# Schematic_Rev2.net
KiCad netlist of a schematic drawn in Altium Designer
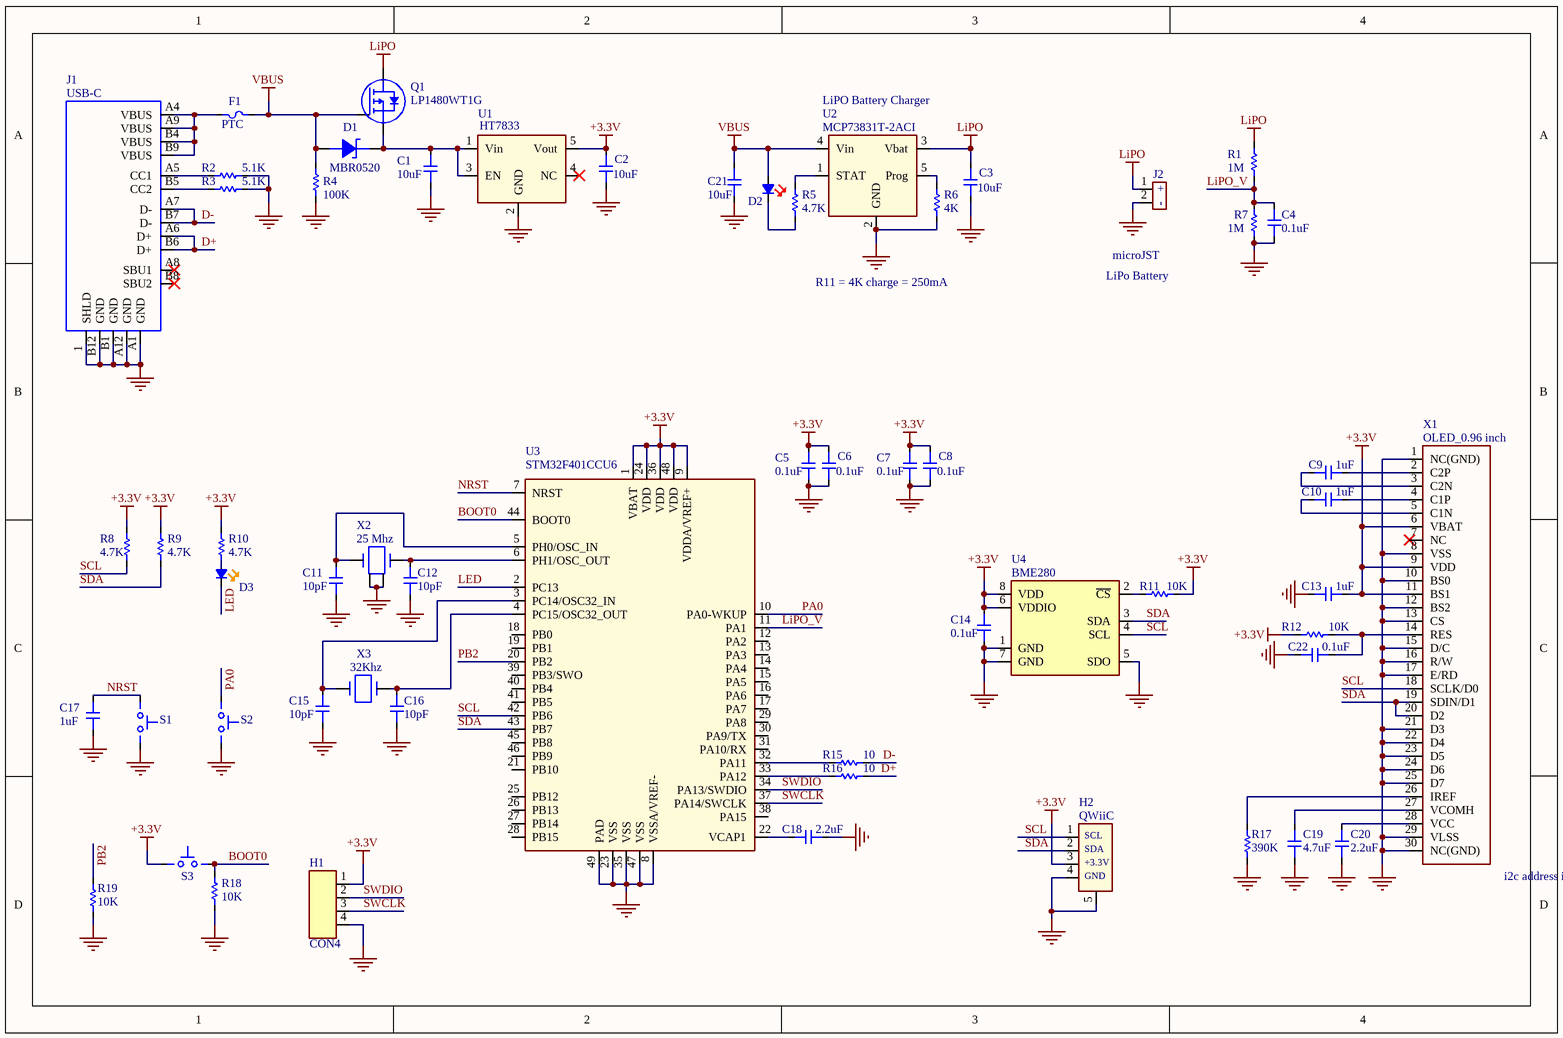
[diagram p0: Schematic_Rev2.SchDoc]

(export (version "E")
  (design (tool "Eeschema 10.0.6"))
  (components
    (comp (ref "C1")
      (value "10uF")
      (footprint "CAPC2012X140N")
      (description "CAP 10uF 0805")
      (libsource (lib "MAR") (part "CAP_0805"))
    )
    (comp (ref "C2")
      (value "10uF")
      (footprint "CAPC2012X140N")
      (description "CAP 10uF 0805")
      (libsource (lib "MAR") (part "CAP_0805"))
    )
    (comp (ref "C3")
      (value "10uF")
      (footprint "CAPC2012X140N")
      (description "CAP 10uF 0805")
      (libsource (lib "MAR") (part "CAP_0805"))
    )
    (comp (ref "C4")
      (value "0.1uF")
      (footprint "CAPC0603X56N")
      (description "CAP 0.1uF 0201")
      (libsource (lib "MAR") (part "CAP_0201"))
    )
    (comp (ref "C5")
      (value "0.1uF")
      (footprint "CAPC1005X56N")
      (description "CAP 0.1uF 0402")
      (libsource (lib "MAR") (part "CAP_0402"))
    )
    (comp (ref "C6")
      (value "0.1uF")
      (footprint "CAPC1005X56N")
      (description "CAP 0.1uF 0402")
      (libsource (lib "MAR") (part "CAP_0402"))
    )
    (comp (ref "C7")
      (value "0.1uF")
      (footprint "CAPC1005X56N")
      (description "CAP 0.1uF 0402")
      (libsource (lib "MAR") (part "CAP_0402"))
    )
    (comp (ref "C8")
      (value "0.1uF")
      (footprint "CAPC1005X56N")
      (description "CAP 0.1uF 0402")
      (libsource (lib "MAR") (part "CAP_0402"))
    )
    (comp (ref "C9")
      (value "1uF")
      (footprint "CAPC1005X56N")
      (description "CAP 1uF 0402")
      (libsource (lib "MAR") (part "CAP_0402"))
    )
    (comp (ref "C10")
      (value "1uF")
      (footprint "CAPC1005X56N")
      (description "CAP 1uF 0402")
      (libsource (lib "MAR") (part "CAP_0402"))
    )
    (comp (ref "C11")
      (value "10pF")
      (footprint "CAPC0603X56N")
      (description "CAP 0.1uF 0201")
      (libsource (lib "MAR") (part "CAP_0201"))
    )
    (comp (ref "C12")
      (value "10pF")
      (footprint "CAPC0603X56N")
      (description "CAP 10pF 0201")
      (libsource (lib "MAR") (part "CAP_0201"))
    )
    (comp (ref "C13")
      (value "1uF")
      (footprint "CAPC1005X56N")
      (description "CAP 1uF 0402")
      (libsource (lib "MAR") (part "CAP_0402"))
    )
    (comp (ref "C14")
      (value "0.1uF")
      (footprint "CAPC0603X56N")
      (description "CAP 0.1uF 0201")
      (libsource (lib "MAR") (part "CAP_0201"))
    )
    (comp (ref "C15")
      (value "10pF")
      (footprint "CAPC0603X56N")
      (description "CAP 0.1uF 0201")
      (libsource (lib "MAR") (part "CAP_0201"))
    )
    (comp (ref "C16")
      (value "10pF")
      (footprint "CAPC0603X56N")
      (description "CAP 10pF 0201")
      (libsource (lib "MAR") (part "CAP_0201"))
    )
    (comp (ref "C17")
      (value "1uF")
      (footprint "CAPC1005X56N")
      (description "CAP 1uF 0402")
      (libsource (lib "MAR") (part "CAP_0402"))
    )
    (comp (ref "C18")
      (value "2.2uF")
      (footprint "CAPC1608X09L")
      (description "CAP 2.2uF 0603")
      (libsource (lib "MAR") (part "CAP_0603"))
    )
    (comp (ref "C19")
      (value "4.7uF")
      (footprint "CAPC1608X09L")
      (description "CAP 4.7uF 0603")
      (libsource (lib "MAR") (part "CAP_0603"))
    )
    (comp (ref "C20")
      (value "2.2uF")
      (footprint "CAPC1608X09L")
      (description "CAP 2.2uF 0603")
      (libsource (lib "MAR") (part "CAP_0603"))
    )
    (comp (ref "C21")
      (value "10uF")
      (footprint "CAPC2012X140N")
      (description "CAP 10uF 0805")
      (libsource (lib "MAR") (part "CAP_0805"))
    )
    (comp (ref "C22")
      (value "0.1uF")
      (footprint "CAPC1005X56N")
      (description "CAP 0.1uF 0402")
      (libsource (lib "MAR") (part "CAP_0402"))
    )
    (comp (ref "D1")
      (value "MBR0520")
      (footprint "SOD123")
      (description "DIODE SCHOTTKY 20V 500MA SOD-123")
      (fields (field (name "MANUFACTURER") "Micro") (field (name "PART_NUMBER") "C78746"))
      (libsource (lib "MAR") (part "MBR0520-TP"))
    )
    (comp (ref "D2")
      (value "Red Led")
      (footprint "LED1005X40N-Red")
      (description "LED Red 0402")
      (fields (field (name "PART_NUMBER") "C364556") (field (name "MANUFACTURER") "Lite-On"))
      (libsource (lib "MAR") (part "LED_0402_SMALL_Red"))
    )
    (comp (ref "D3")
      (value "~")
      (footprint "LED1005X40N-Orange")
      (description "LED Orange 0402")
      (fields (field (name "MANUFACTURER") "Lite-On") (field (name "PART_NUMBER") "C364554"))
      (libsource (lib "MAR") (part "LED_0402_SMALL_Orange"))
    )
    (comp (ref "F1")
      (value "PTC")
      (footprint "RESC1608X06L (0603 FOOTPRINT)")
      (description "PTC FUSE 0.5mA hold, 1A trip 0603")
      (fields (field (name "MANUFACTURER") "JDT Fuse") (field (name "PART_NUMBER") "C2982257"))
      (libsource (lib "MAR") (part "PTC_FUSE_0603"))
    )
    (comp (ref "H1")
      (value "CON4")
      (footprint "HDR1X4-Empty")
      (description "CONN HEADER 4POS .100\" PADS")
      (fields (field (name "PART_NUMBER") "PADS"))
      (libsource (lib "MAR") (part "CON4"))
    )
    (comp (ref "H2")
      (value "QWiiC")
      (footprint "SM04B-SRSS-TB")
      (description "CONN HEADER 4POS .100 R/A QWIIC")
      (fields (field (name "MANUFACTURER") "JST") (field (name "PART_NUMBER") "PRT-14417"))
      (libsource (lib "MAR") (part "SM04B-SRSS-TB"))
    )
    (comp (ref "J1")
      (value "USB-C")
      (footprint "TYPE-C-31-M-12")
      (description "CONN RECPT USB-C")
      (fields (field (name "MANUFACTURER") "KHE") (field (name "PART_NUMBER") "C165948"))
      (libsource (lib "MAR") (part "USB-C"))
    )
    (comp (ref "J2")
      (value "CON2")
      (footprint "JST_Micro_2PIN")
      (description "JST MIcro CONN 2POS")
      (libsource (lib "MAR") (part "JST_Micro_CONN_2PIN"))
    )
    (comp (ref "Q1")
      (value "LP1480WT1G")
      (footprint "SC-70")
      (description "MOSFET P-CH 20V 1.4A SC-70")
      (fields (field (name "MANUFACTURER") "LRC") (field (name "PART_NUMBER") "C172434"))
      (libsource (lib "MAR") (part "LP1480WT1G"))
    )
    (comp (ref "R1")
      (value "1M")
      (footprint "RESC0603X40L (0201 footprint)")
      (description "RES 1M 0201")
      (libsource (lib "MAR") (part "RES_0201"))
    )
    (comp (ref "R2")
      (value "5.1K")
      (footprint "RESC0603X40L (0201 footprint)")
      (description "RES 0201 5.1K")
      (libsource (lib "MAR") (part "RES_0201"))
    )
    (comp (ref "R3")
      (value "5.1K")
      (footprint "RESC0603X40L (0201 footprint)")
      (description "RES 0201 5.1K")
      (libsource (lib "MAR") (part "RES_0201"))
    )
    (comp (ref "R4")
      (value "100K")
      (footprint "RESC0603X40L (0201 footprint)")
      (description "RES 100K 0201")
      (libsource (lib "MAR") (part "RES_0201"))
    )
    (comp (ref "R5")
      (value "4.7K")
      (footprint "RESC0603X40L (0201 footprint)")
      (description "RES 4.7K 0201")
      (libsource (lib "MAR") (part "RES_0201"))
    )
    (comp (ref "R6")
      (value "4K")
      (footprint "RESC0603X40L (0201 footprint)")
      (description "RES 4K 0201")
      (libsource (lib "MAR") (part "RES_0201"))
    )
    (comp (ref "R7")
      (value "1M")
      (footprint "RESC0603X40L (0201 footprint)")
      (description "RES 1M 0201")
      (libsource (lib "MAR") (part "RES_0201"))
    )
    (comp (ref "R8")
      (value "4.7K")
      (footprint "RESC0603X40L (0201 footprint)")
      (description "RES 4.7K 0201")
      (libsource (lib "MAR") (part "RES_0201"))
    )
    (comp (ref "R9")
      (value "4.7K")
      (footprint "RESC0603X40L (0201 footprint)")
      (description "RES 4.7K 0201")
      (libsource (lib "MAR") (part "RES_0201"))
    )
    (comp (ref "R10")
      (value "4.7K")
      (footprint "RESC0603X40L (0201 footprint)")
      (description "RES 4.7K 0201")
      (libsource (lib "MAR") (part "RES_0201"))
    )
    (comp (ref "R11")
      (value "10K")
      (footprint "RESC0603X40L (0201 footprint)")
      (description "RES 10K 0201")
      (libsource (lib "MAR") (part "RES_0201"))
    )
    (comp (ref "R12")
      (value "10K")
      (footprint "RESC0603X40L (0201 footprint)")
      (description "RES 10K 0201")
      (libsource (lib "MAR") (part "RES_0201"))
    )
    (comp (ref "R15")
      (value "10")
      (footprint "RESC0603X40L (0201 footprint)")
      (description "RES 10 0201")
      (libsource (lib "MAR") (part "RES_0201"))
    )
    (comp (ref "R16")
      (value "10")
      (footprint "RESC0603X40L (0201 footprint)")
      (description "RES 10 0201")
      (libsource (lib "MAR") (part "RES_0201"))
    )
    (comp (ref "R17")
      (value "390K")
      (footprint "RESC0603X40L (0201 footprint)")
      (description "RES 390K 0201")
      (libsource (lib "MAR") (part "RES_0201"))
    )
    (comp (ref "R18")
      (value "10K")
      (footprint "RESC0603X40L (0201 footprint)")
      (description "RES 10K 0201")
      (libsource (lib "MAR") (part "RES_0201"))
    )
    (comp (ref "R19")
      (value "10K")
      (footprint "RESC0603X40L (0201 footprint)")
      (description "RES 10K 0201")
      (libsource (lib "MAR") (part "RES_0201"))
    )
    (comp (ref "S1")
      (value "~")
      (footprint "TS-1088R-02526")
      (description "Tactile Micro Switch")
      (fields (field (name "PART_NUMBER") "C455281") (field (name "MANUFACTURER") "XUNPU"))
      (libsource (lib "MAR") (part "TS-1088R-02526"))
    )
    (comp (ref "S2")
      (value "~")
      (footprint "TS-1088R-02526")
      (description "Tactile Micro Switch")
      (fields (field (name "PART_NUMBER") "C455281") (field (name "MANUFACTURER") "XUNPU"))
      (libsource (lib "MAR") (part "TS-1088R-02526"))
    )
    (comp (ref "S3")
      (value "~")
      (footprint "TS-1088R-02526")
      (description "Tactile Micro Switch")
      (fields (field (name "PART_NUMBER") "C455281") (field (name "MANUFACTURER") "XUNPU"))
      (libsource (lib "MAR") (part "TS-1088R-02526"))
    )
    (comp (ref "U1")
      (value "HT7833")
      (footprint "SOT95P280X144-5N")
      (description "IC LDO 3.3V 0.5A SOT23-5")
      (fields (field (name "MANUFACTURER") "Holtek") (field (name "PART_NUMBER") "C164106"))
      (libsource (lib "MAR") (part "HT7833"))
    )
    (comp (ref "U2")
      (value "MCP73831T-2ACI")
      (footprint "SOT95P280X144-5N")
      (description "Charger IC Lithium-Ion/Polymer SOT23-5")
      (fields (field (name "MANUFACTURER") "Microchip") (field (name "PART_NUMBER") "MCP73831T-2ACI/OT"))
      (libsource (lib "MAR") (part "MCP73831T-2ACI/OT"))
    )
    (comp (ref "U3")
      (value "STM32F401CCU6")
      (footprint "QFN48_NEWEST 0.5mm pitch")
      (description "IC MCU 32BIT 256KB FLASH 48LQFN")
      (fields (field (name "MANUFACTURER") "ST Micro"))
      (libsource (lib "MAR") (part "STM32F401CCU6"))
    )
    (comp (ref "U4")
      (value "BME280")
      (footprint "LGA2.5X2.5-8N")
      (description "Gas, Humidity, Pressure, Temperature Sensor I2C,")
      (fields (field (name "MANUFACTURER") "Bosch"))
      (libsource (lib "MAR") (part "BME280"))
    )
    (comp (ref "X1")
      (value "OLED_0.96 inch")
      (footprint "OLED_GLASS 0.96 INCH_TOPSIDE")
      (description "0.96 inch OLED_GLASS")
      (fields (field (name "PART_NUMBER") "ER-OLED0.96-3W") (field (name "MANUFACTURER") "Buy-Display"))
      (libsource (lib "MAR") (part "OLED_GLASS 0.96 inch"))
    )
    (comp (ref "X2")
      (value "25 Mhz")
      (footprint "OSC20X16")
      (description "CRYSTAL 25MHZ 10PF SMD")
      (fields (field (name "PART_NUMBER") "ECS-250-10-37B2-CTN-TR") (field (name "MANUFACTURER") "ECS"))
      (libsource (lib "MAR") (part "25Mhz"))
    )
    (comp (ref "X3")
      (value "32Khz")
      (footprint "TJXM32768K2TGDCNT2T")
      (description "CRYSTAL 32.768 KHZ 12.5PF SMD")
      (fields (field (name "PART_NUMBER") "TJXM32768K2TGDCNT2T") (field (name "MANUFACTURER") "TAE"))
      (libsource (lib "MAR") (part "TJXM32768K2TGDCNT2T"))
    )
  )
  (nets
    (net (code "1") (name "+3.3V") (class "Default")
      (node (ref "C13") (pin "2") (pintype "passive"))
      (node (ref "C14") (pin "1") (pintype "passive"))
      (node (ref "C2") (pin "1") (pintype "passive"))
      (node (ref "C5") (pin "2") (pintype "passive"))
      (node (ref "C6") (pin "2") (pintype "passive"))
      (node (ref "C7") (pin "2") (pintype "passive"))
      (node (ref "C8") (pin "2") (pintype "passive"))
      (node (ref "H1") (pin "1") (pintype "passive"))
      (node (ref "H2") (pin "3") (pintype "passive"))
      (node (ref "R10") (pin "1") (pintype "passive"))
      (node (ref "R11") (pin "2") (pintype "passive"))
      (node (ref "R12") (pin "1") (pintype "passive"))
      (node (ref "R8") (pin "1") (pintype "passive"))
      (node (ref "R9") (pin "1") (pintype "passive"))
      (node (ref "S3") (pin "1") (pinfunction "A_1") (pintype "passive"))
      (node (ref "U1") (pin "5") (pinfunction "Vout_5") (pintype "passive"))
      (node (ref "U3") (pin "1") (pinfunction "VBAT_1") (pintype "power_in"))
      (node (ref "U3") (pin "24") (pinfunction "VDD_24") (pintype "power_in"))
      (node (ref "U3") (pin "36") (pinfunction "VDD_36") (pintype "power_in"))
      (node (ref "U3") (pin "48") (pinfunction "VDD_48") (pintype "power_in"))
      (node (ref "U3") (pin "9") (pinfunction "VDDA/VREF+_9") (pintype "power_in"))
      (node (ref "U4") (pin "6") (pinfunction "VDDIO_6") (pintype "power_in"))
      (node (ref "U4") (pin "8") (pinfunction "VDD_8") (pintype "power_in"))
      (node (ref "X1") (pin "11") (pinfunction "BS1_11") (pintype "passive"))
      (node (ref "X1") (pin "6") (pinfunction "VBAT_6") (pintype "passive"))
      (node (ref "X1") (pin "9") (pinfunction "VDD_9") (pintype "passive"))
    )
    (net (code "2") (name "/BOOT0") (class "Default")
      (node (ref "R18") (pin "1") (pintype "passive"))
      (node (ref "S3") (pin "2") (pinfunction "B_2") (pintype "passive"))
      (node (ref "U3") (pin "44") (pinfunction "BOOT0_44") (pintype "passive"))
    )
    (net (code "3") (name "/D+") (class "Default")
      (node (ref "J1") (pin "A6") (pinfunction "D+_A6") (pintype "power_in"))
      (node (ref "J1") (pin "B6") (pinfunction "D+_B6") (pintype "power_in"))
      (node (ref "R16") (pin "2") (pintype "passive"))
    )
    (net (code "4") (name "/D-") (class "Default")
      (node (ref "J1") (pin "A7") (pinfunction "D-_A7") (pintype "power_in"))
      (node (ref "J1") (pin "B7") (pinfunction "D-_B7") (pintype "power_in"))
      (node (ref "R15") (pin "2") (pintype "passive"))
    )
    (net (code "5") (name "/LED") (class "Default")
      (node (ref "D3") (pin "1") (pintype "passive"))
      (node (ref "U3") (pin "2") (pinfunction "PC13_2") (pintype "passive"))
    )
    (net (code "6") (name "/LiPO_V") (class "Default")
      (node (ref "C4") (pin "1") (pintype "passive"))
      (node (ref "R1") (pin "1") (pintype "passive"))
      (node (ref "R7") (pin "2") (pintype "passive"))
      (node (ref "U3") (pin "11") (pinfunction "PA1_11") (pintype "passive"))
    )
    (net (code "7") (name "/NRST") (class "Default")
      (node (ref "C17") (pin "2") (pintype "passive"))
      (node (ref "S1") (pin "1") (pinfunction "A_1") (pintype "passive"))
      (node (ref "U3") (pin "7") (pinfunction "NRST_7") (pintype "passive"))
    )
    (net (code "8") (name "/PA0") (class "Default")
      (node (ref "S2") (pin "1") (pinfunction "A_1") (pintype "passive"))
      (node (ref "U3") (pin "10") (pinfunction "PA0-WKUP_10") (pintype "passive"))
    )
    (net (code "9") (name "/PB2") (class "Default")
      (node (ref "R19") (pin "2") (pintype "passive"))
      (node (ref "U3") (pin "20") (pinfunction "PB2_20") (pintype "passive"))
    )
    (net (code "10") (name "/SCL") (class "Default")
      (node (ref "H2") (pin "1") (pintype "passive"))
      (node (ref "R8") (pin "2") (pintype "passive"))
      (node (ref "U3") (pin "42") (pinfunction "PB6_42") (pintype "passive"))
      (node (ref "U4") (pin "4") (pinfunction "SCL_4") (pintype "passive"))
      (node (ref "X1") (pin "18") (pinfunction "SCLK/D0_18") (pintype "passive"))
    )
    (net (code "11") (name "/SDA") (class "Default")
      (node (ref "H2") (pin "2") (pintype "passive"))
      (node (ref "R9") (pin "2") (pintype "passive"))
      (node (ref "U3") (pin "43") (pinfunction "PB7_43") (pintype "passive"))
      (node (ref "U4") (pin "3") (pinfunction "SDA_3") (pintype "passive"))
      (node (ref "X1") (pin "19") (pinfunction "SDIN/D1_19") (pintype "passive"))
      (node (ref "X1") (pin "20") (pinfunction "D2_20") (pintype "passive"))
    )
    (net (code "12") (name "/SWCLK") (class "Default")
      (node (ref "H1") (pin "3") (pintype "passive"))
      (node (ref "U3") (pin "37") (pinfunction "PA14/SWCLK_37") (pintype "passive"))
    )
    (net (code "13") (name "/SWDIO") (class "Default")
      (node (ref "H1") (pin "2") (pintype "passive"))
      (node (ref "U3") (pin "34") (pinfunction "PA13/SWDIO_34") (pintype "passive"))
    )
    (net (code "14") (name "GND") (class "Default")
      (node (ref "C1") (pin "2") (pintype "passive"))
      (node (ref "C11") (pin "2") (pintype "passive"))
      (node (ref "C12") (pin "2") (pintype "passive"))
      (node (ref "C13") (pin "1") (pintype "passive"))
      (node (ref "C14") (pin "2") (pintype "passive"))
      (node (ref "C15") (pin "2") (pintype "passive"))
      (node (ref "C16") (pin "2") (pintype "passive"))
      (node (ref "C17") (pin "1") (pintype "passive"))
      (node (ref "C18") (pin "2") (pintype "passive"))
      (node (ref "C19") (pin "1") (pintype "passive"))
      (node (ref "C2") (pin "2") (pintype "passive"))
      (node (ref "C20") (pin "2") (pintype "passive"))
      (node (ref "C21") (pin "2") (pintype "passive"))
      (node (ref "C22") (pin "2") (pintype "passive"))
      (node (ref "C3") (pin "2") (pintype "passive"))
      (node (ref "C4") (pin "2") (pintype "passive"))
      (node (ref "C5") (pin "1") (pintype "passive"))
      (node (ref "C6") (pin "1") (pintype "passive"))
      (node (ref "C7") (pin "1") (pintype "passive"))
      (node (ref "C8") (pin "1") (pintype "passive"))
      (node (ref "H1") (pin "4") (pintype "passive"))
      (node (ref "H2") (pin "4") (pintype "passive"))
      (node (ref "H2") (pin "5") (pintype "passive"))
      (node (ref "J1") (pin "1") (pinfunction "SHLD_1") (pintype "power_in"))
      (node (ref "J1") (pin "A1") (pinfunction "GND_A1") (pintype "power_in"))
      (node (ref "J1") (pin "A12") (pinfunction "GND_A12") (pintype "power_in"))
      (node (ref "J1") (pin "B1") (pinfunction "GND_B1") (pintype "power_in"))
      (node (ref "J1") (pin "B12") (pinfunction "GND_B12") (pintype "passive"))
      (node (ref "J2") (pin "2") (pintype "passive"))
      (node (ref "R17") (pin "1") (pintype "passive"))
      (node (ref "R18") (pin "2") (pintype "passive"))
      (node (ref "R19") (pin "1") (pintype "passive"))
      (node (ref "R2") (pin "1") (pintype "passive"))
      (node (ref "R3") (pin "1") (pintype "passive"))
      (node (ref "R4") (pin "2") (pintype "passive"))
      (node (ref "R6") (pin "1") (pintype "passive"))
      (node (ref "R7") (pin "1") (pintype "passive"))
      (node (ref "S1") (pin "2") (pinfunction "B_2") (pintype "passive"))
      (node (ref "S2") (pin "2") (pinfunction "B_2") (pintype "passive"))
      (node (ref "U1") (pin "2") (pinfunction "GND_2") (pintype "power_in"))
      (node (ref "U2") (pin "2") (pinfunction "GND_2") (pintype "power_in"))
      (node (ref "U3") (pin "23") (pinfunction "VSS_23") (pintype "power_in"))
      (node (ref "U3") (pin "35") (pinfunction "VSS_35") (pintype "power_in"))
      (node (ref "U3") (pin "47") (pinfunction "VSS_47") (pintype "power_in"))
      (node (ref "U3") (pin "49") (pinfunction "PAD_49") (pintype "power_in"))
      (node (ref "U3") (pin "8") (pinfunction "VSSA/VREF-_8") (pintype "power_in"))
      (node (ref "U4") (pin "1") (pinfunction "GND_1") (pintype "power_in"))
      (node (ref "U4") (pin "5") (pinfunction "SDO_5") (pintype "passive"))
      (node (ref "U4") (pin "7") (pinfunction "GND_7") (pintype "power_in"))
      (node (ref "X1") (pin "1") (pinfunction "NC(GND)_1") (pintype "passive"))
      (node (ref "X1") (pin "10") (pinfunction "BS0_10") (pintype "passive"))
      (node (ref "X1") (pin "12") (pinfunction "BS2_12") (pintype "passive"))
      (node (ref "X1") (pin "13") (pinfunction "CS_13") (pintype "passive"))
      (node (ref "X1") (pin "15") (pinfunction "D/C_15") (pintype "passive"))
      (node (ref "X1") (pin "16") (pinfunction "R/W_16") (pintype "passive"))
      (node (ref "X1") (pin "17") (pinfunction "E/RD_17") (pintype "passive"))
      (node (ref "X1") (pin "21") (pinfunction "D3_21") (pintype "passive"))
      (node (ref "X1") (pin "22") (pinfunction "D4_22") (pintype "passive"))
      (node (ref "X1") (pin "23") (pinfunction "D5_23") (pintype "passive"))
      (node (ref "X1") (pin "24") (pinfunction "D6_24") (pintype "passive"))
      (node (ref "X1") (pin "25") (pinfunction "D7_25") (pintype "passive"))
      (node (ref "X1") (pin "29") (pinfunction "VLSS_29") (pintype "passive"))
      (node (ref "X1") (pin "30") (pinfunction "NC(GND)_30") (pintype "passive"))
      (node (ref "X1") (pin "8") (pinfunction "VSS_8") (pintype "passive"))
      (node (ref "X2") (pin "2") (pinfunction "2_2") (pintype "power_in"))
      (node (ref "X2") (pin "4") (pinfunction "4_4") (pintype "power_in"))
    )
    (net (code "15") (name "LiPO") (class "Default")
      (node (ref "C3") (pin "1") (pintype "passive"))
      (node (ref "J2") (pin "1") (pintype "passive"))
      (node (ref "Q1") (pin "3") (pinfunction "D_3") (pintype "passive"))
      (node (ref "R1") (pin "2") (pintype "passive"))
      (node (ref "U2") (pin "3") (pinfunction "Vbat_3") (pintype "passive"))
    )
    (net (code "16") (name "Net-(D1-Cathode)") (class "Default")
      (node (ref "C1") (pin "1") (pintype "passive"))
      (node (ref "D1") (pin "1") (pinfunction "Cathode_1") (pintype "passive"))
      (node (ref "Q1") (pin "2") (pinfunction "S_2") (pintype "passive"))
      (node (ref "U1") (pin "1") (pinfunction "Vin_1") (pintype "passive"))
      (node (ref "U1") (pin "3") (pinfunction "EN_3") (pintype "passive"))
    )
    (net (code "17") (name "Net-(D2-Pad1)") (class "Default")
      (node (ref "D2") (pin "1") (pintype "passive"))
      (node (ref "R5") (pin "1") (pintype "passive"))
    )
    (net (code "18") (name "Net-(D3-Pad2)") (class "Default")
      (node (ref "D3") (pin "2") (pintype "passive"))
      (node (ref "R10") (pin "2") (pintype "passive"))
    )
    (net (code "19") (name "Net-(F1-Pad2)") (class "Default")
      (node (ref "F1") (pin "2") (pintype "passive"))
      (node (ref "J1") (pin "A4") (pinfunction "VBUS_A4") (pintype "passive"))
      (node (ref "J1") (pin "A9") (pinfunction "VBUS_A9") (pintype "power_in"))
      (node (ref "J1") (pin "B4") (pinfunction "VBUS_B4") (pintype "power_in"))
      (node (ref "J1") (pin "B9") (pinfunction "VBUS_B9") (pintype "passive"))
    )
    (net (code "20") (name "Net-(J1-CC1)") (class "Default")
      (node (ref "J1") (pin "A5") (pinfunction "CC1_A5") (pintype "power_in"))
      (node (ref "R2") (pin "2") (pintype "passive"))
    )
    (net (code "21") (name "Net-(J1-CC2)") (class "Default")
      (node (ref "J1") (pin "B5") (pinfunction "CC2_B5") (pintype "power_in"))
      (node (ref "R3") (pin "2") (pintype "passive"))
    )
    (net (code "22") (name "Net-(U2-Prog)") (class "Default")
      (node (ref "R6") (pin "2") (pintype "passive"))
      (node (ref "U2") (pin "5") (pinfunction "Prog_5") (pintype "passive"))
    )
    (net (code "23") (name "Net-(U2-STAT)") (class "Default")
      (node (ref "R5") (pin "2") (pintype "passive"))
      (node (ref "U2") (pin "1") (pinfunction "STAT_1") (pintype "passive"))
    )
    (net (code "24") (name "Net-(U3-PA11)") (class "Default")
      (node (ref "R15") (pin "1") (pintype "passive"))
      (node (ref "U3") (pin "32") (pinfunction "PA11_32") (pintype "passive"))
    )
    (net (code "25") (name "Net-(U3-PA12)") (class "Default")
      (node (ref "R16") (pin "1") (pintype "passive"))
      (node (ref "U3") (pin "33") (pinfunction "PA12_33") (pintype "passive"))
    )
    (net (code "26") (name "Net-(U3-PC14{slash}OSC32_IN)") (class "Default")
      (node (ref "C15") (pin "1") (pintype "passive"))
      (node (ref "U3") (pin "3") (pinfunction "PC14/OSC32_IN_3") (pintype "passive"))
      (node (ref "X3") (pin "1") (pinfunction "1_1") (pintype "passive"))
    )
    (net (code "27") (name "Net-(U3-PC15{slash}OSC32_OUT)") (class "Default")
      (node (ref "C16") (pin "1") (pintype "passive"))
      (node (ref "U3") (pin "4") (pinfunction "PC15/OSC32_OUT_4") (pintype "passive"))
      (node (ref "X3") (pin "2") (pinfunction "2_2") (pintype "passive"))
    )
    (net (code "28") (name "Net-(U3-PH0{slash}OSC_IN)") (class "Default")
      (node (ref "C11") (pin "1") (pintype "passive"))
      (node (ref "U3") (pin "5") (pinfunction "PH0/OSC_IN_5") (pintype "passive"))
      (node (ref "X2") (pin "1") (pinfunction "1_1") (pintype "passive"))
    )
    (net (code "29") (name "Net-(U3-PH1{slash}OSC_OUT)") (class "Default")
      (node (ref "C12") (pin "1") (pintype "passive"))
      (node (ref "U3") (pin "6") (pinfunction "PH1/OSC_OUT_6") (pintype "passive"))
      (node (ref "X2") (pin "3") (pinfunction "3_3") (pintype "passive"))
    )
    (net (code "30") (name "Net-(U3-VCAP1)") (class "Default")
      (node (ref "C18") (pin "1") (pintype "passive"))
      (node (ref "U3") (pin "22") (pinfunction "VCAP1_22") (pintype "passive"))
    )
    (net (code "31") (name "Net-(U4-~{CS})") (class "Default")
      (node (ref "R11") (pin "1") (pintype "passive"))
      (node (ref "U4") (pin "2") (pinfunction "~{CS}_2") (pintype "passive"))
    )
    (net (code "32") (name "Net-(X1-C1N)") (class "Default")
      (node (ref "C10") (pin "1") (pintype "passive"))
      (node (ref "X1") (pin "5") (pinfunction "C1N_5") (pintype "passive"))
    )
    (net (code "33") (name "Net-(X1-C1P)") (class "Default")
      (node (ref "C10") (pin "2") (pintype "passive"))
      (node (ref "X1") (pin "4") (pinfunction "C1P_4") (pintype "passive"))
    )
    (net (code "34") (name "Net-(X1-C2N)") (class "Default")
      (node (ref "C9") (pin "1") (pintype "passive"))
      (node (ref "X1") (pin "3") (pinfunction "C2N_3") (pintype "passive"))
    )
    (net (code "35") (name "Net-(X1-C2P)") (class "Default")
      (node (ref "C9") (pin "2") (pintype "passive"))
      (node (ref "X1") (pin "2") (pinfunction "C2P_2") (pintype "passive"))
    )
    (net (code "36") (name "Net-(X1-IREF)") (class "Default")
      (node (ref "R17") (pin "2") (pintype "passive"))
      (node (ref "X1") (pin "26") (pinfunction "IREF_26") (pintype "passive"))
    )
    (net (code "37") (name "Net-(X1-RES)") (class "Default")
      (node (ref "C22") (pin "1") (pintype "passive"))
      (node (ref "R12") (pin "2") (pintype "passive"))
      (node (ref "X1") (pin "14") (pinfunction "RES_14") (pintype "passive"))
    )
    (net (code "38") (name "Net-(X1-VCC)") (class "Default")
      (node (ref "C20") (pin "1") (pintype "passive"))
      (node (ref "X1") (pin "28") (pinfunction "VCC_28") (pintype "passive"))
    )
    (net (code "39") (name "Net-(X1-VCOMH)") (class "Default")
      (node (ref "C19") (pin "2") (pintype "passive"))
      (node (ref "X1") (pin "27") (pinfunction "VCOMH_27") (pintype "passive"))
    )
    (net (code "40") (name "VBUS") (class "Default")
      (node (ref "C21") (pin "1") (pintype "passive"))
      (node (ref "D1") (pin "2") (pinfunction "Annode_2") (pintype "passive"))
      (node (ref "D2") (pin "2") (pintype "passive"))
      (node (ref "F1") (pin "1") (pintype "passive"))
      (node (ref "Q1") (pin "1") (pinfunction "G_1") (pintype "passive"))
      (node (ref "R4") (pin "1") (pintype "passive"))
      (node (ref "U2") (pin "4") (pinfunction "Vin_4") (pintype "passive"))
    )
    (net (code "41") (name "unconnected-(J1-SBU1-PadA8)") (class "Default")
      (node (ref "J1") (pin "A8") (pinfunction "SBU1_A8") (pintype "power_in+no_connect"))
    )
    (net (code "42") (name "unconnected-(J1-SBU2-PadB8)") (class "Default")
      (node (ref "J1") (pin "B8") (pinfunction "SBU2_B8") (pintype "power_in+no_connect"))
    )
    (net (code "43") (name "unconnected-(U1-NC-Pad4)") (class "Default")
      (node (ref "U1") (pin "4") (pinfunction "NC_4") (pintype "passive+no_connect"))
    )
    (net (code "44") (name "unconnected-(U3-PA2-Pad12)") (class "Default")
      (node (ref "U3") (pin "12") (pinfunction "PA2_12") (pintype "passive"))
    )
    (net (code "45") (name "unconnected-(U3-PA3-Pad13)") (class "Default")
      (node (ref "U3") (pin "13") (pinfunction "PA3_13") (pintype "passive"))
    )
    (net (code "46") (name "unconnected-(U3-PA4-Pad14)") (class "Default")
      (node (ref "U3") (pin "14") (pinfunction "PA4_14") (pintype "passive"))
    )
    (net (code "47") (name "unconnected-(U3-PA5-Pad15)") (class "Default")
      (node (ref "U3") (pin "15") (pinfunction "PA5_15") (pintype "passive"))
    )
    (net (code "48") (name "unconnected-(U3-PA6-Pad16)") (class "Default")
      (node (ref "U3") (pin "16") (pinfunction "PA6_16") (pintype "passive"))
    )
    (net (code "49") (name "unconnected-(U3-PA7-Pad17)") (class "Default")
      (node (ref "U3") (pin "17") (pinfunction "PA7_17") (pintype "passive"))
    )
    (net (code "50") (name "unconnected-(U3-PA8-Pad29)") (class "Default")
      (node (ref "U3") (pin "29") (pinfunction "PA8_29") (pintype "passive"))
    )
    (net (code "51") (name "unconnected-(U3-PA9{slash}TX-Pad30)") (class "Default")
      (node (ref "U3") (pin "30") (pinfunction "PA9/TX_30") (pintype "passive"))
    )
    (net (code "52") (name "unconnected-(U3-PA10{slash}RX-Pad31)") (class "Default")
      (node (ref "U3") (pin "31") (pinfunction "PA10/RX_31") (pintype "passive"))
    )
    (net (code "53") (name "unconnected-(U3-PA15-Pad38)") (class "Default")
      (node (ref "U3") (pin "38") (pinfunction "PA15_38") (pintype "passive"))
    )
    (net (code "54") (name "unconnected-(U3-PB0-Pad18)") (class "Default")
      (node (ref "U3") (pin "18") (pinfunction "PB0_18") (pintype "passive"))
    )
    (net (code "55") (name "unconnected-(U3-PB1-Pad19)") (class "Default")
      (node (ref "U3") (pin "19") (pinfunction "PB1_19") (pintype "passive"))
    )
    (net (code "56") (name "unconnected-(U3-PB3{slash}SWO-Pad39)") (class "Default")
      (node (ref "U3") (pin "39") (pinfunction "PB3/SWO_39") (pintype "passive"))
    )
    (net (code "57") (name "unconnected-(U3-PB4-Pad40)") (class "Default")
      (node (ref "U3") (pin "40") (pinfunction "PB4_40") (pintype "passive"))
    )
    (net (code "58") (name "unconnected-(U3-PB5-Pad41)") (class "Default")
      (node (ref "U3") (pin "41") (pinfunction "PB5_41") (pintype "passive"))
    )
    (net (code "59") (name "unconnected-(U3-PB8-Pad45)") (class "Default")
      (node (ref "U3") (pin "45") (pinfunction "PB8_45") (pintype "passive"))
    )
    (net (code "60") (name "unconnected-(U3-PB9-Pad46)") (class "Default")
      (node (ref "U3") (pin "46") (pinfunction "PB9_46") (pintype "passive"))
    )
    (net (code "61") (name "unconnected-(U3-PB10-Pad21)") (class "Default")
      (node (ref "U3") (pin "21") (pinfunction "PB10_21") (pintype "passive"))
    )
    (net (code "62") (name "unconnected-(U3-PB12-Pad25)") (class "Default")
      (node (ref "U3") (pin "25") (pinfunction "PB12_25") (pintype "passive"))
    )
    (net (code "63") (name "unconnected-(U3-PB13-Pad26)") (class "Default")
      (node (ref "U3") (pin "26") (pinfunction "PB13_26") (pintype "passive"))
    )
    (net (code "64") (name "unconnected-(U3-PB14-Pad27)") (class "Default")
      (node (ref "U3") (pin "27") (pinfunction "PB14_27") (pintype "passive"))
    )
    (net (code "65") (name "unconnected-(U3-PB15-Pad28)") (class "Default")
      (node (ref "U3") (pin "28") (pinfunction "PB15_28") (pintype "passive"))
    )
    (net (code "66") (name "unconnected-(X1-NC-Pad7)") (class "Default")
      (node (ref "X1") (pin "7") (pinfunction "NC_7") (pintype "passive+no_connect"))
    )
  )
)
